# nanowii-i2c-mounting-board.net
KiCad netlist of a schematic drawn in EAGLE
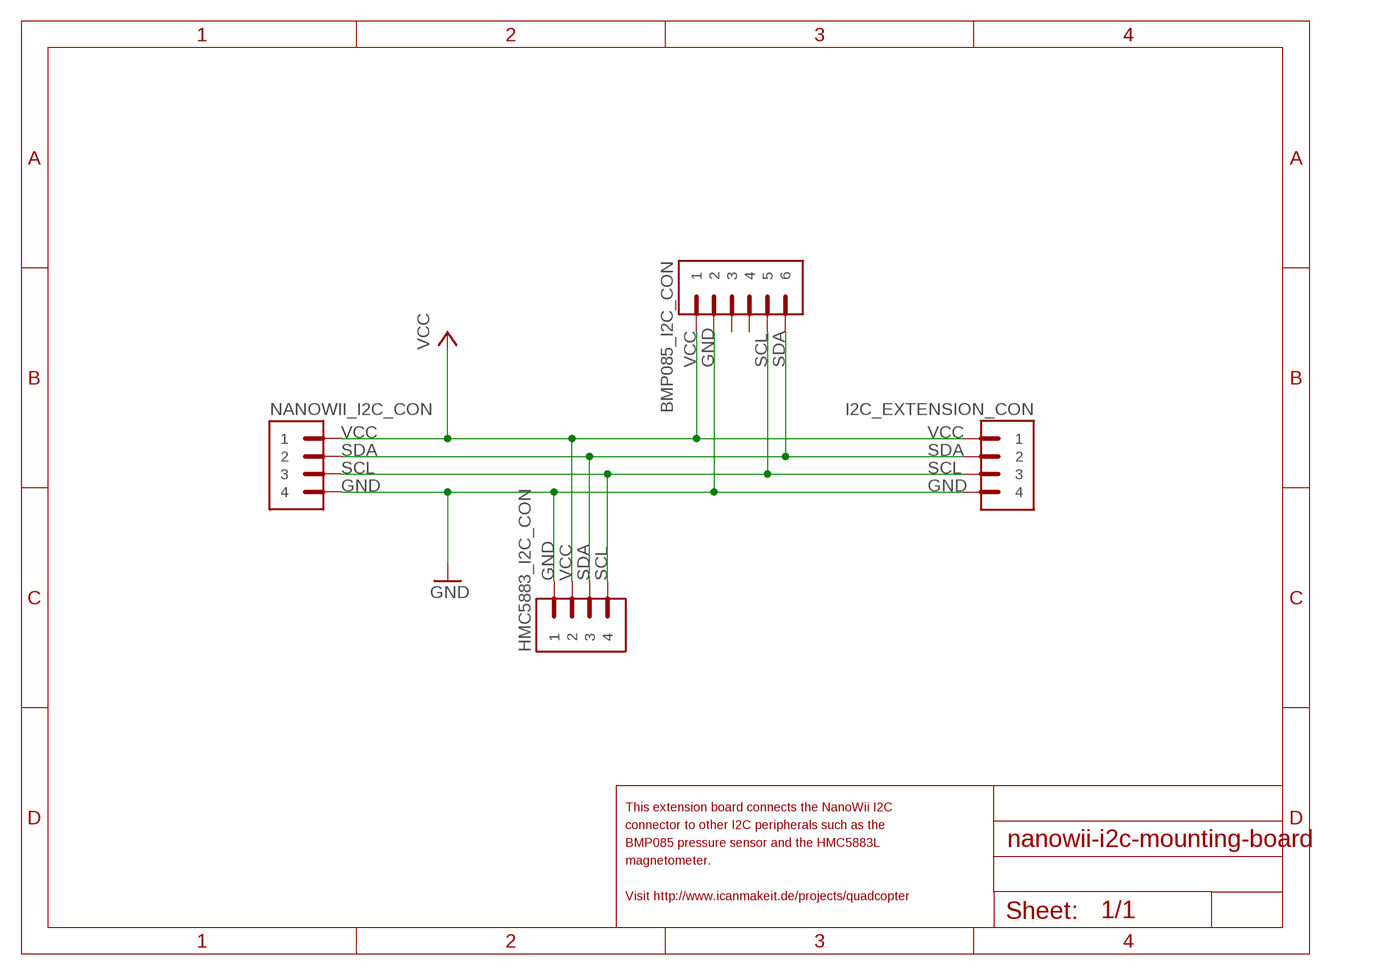
[diagram p0: schematic, sheet 1]

(export (version "E")
  (design (tool "Eeschema 10.0.6"))
  (components
    (comp (ref "BMP085_I2C_CON")
      (value "PIN_HEADER_6-WIDE")
      (footprint "eagle-import:BREAKAWAY_STRAIGHT_6_WIDE")
      (libsource (lib "eagle-import") (part "PIN_HEADER_6-WIDE"))
    )
    (comp (ref "HMC5883_I2C_CON")
      (value "PIN_HEADER_4-WIDE")
      (footprint "eagle-import:BREAKAWAY_STRAIGHT_4_WIDE")
      (libsource (lib "eagle-import") (part "PIN_HEADER_4-WIDE"))
    )
    (comp (ref "I2C_EXTENSION_CON")
      (value "PIN_HEADER_4-WIDE")
      (footprint "eagle-import:BREAKAWAY_STRAIGHT_4_WIDE")
      (libsource (lib "eagle-import") (part "PIN_HEADER_4-WIDE"))
    )
    (comp (ref "NANOWII_I2C_CON")
      (value "PIN_HEADER_4-WIDE")
      (footprint "eagle-import:BREAKAWAY_STRAIGHT_4_WIDE")
      (libsource (lib "eagle-import") (part "PIN_HEADER_4-WIDE"))
    )
  )
  (nets
    (net (code "1") (name "/SCL") (class "Default")
      (node (ref "BMP085_I2C_CON") (pin "5") (pinfunction "5_5") (pintype "passive"))
      (node (ref "HMC5883_I2C_CON") (pin "4") (pinfunction "4_4") (pintype "bidirectional"))
      (node (ref "I2C_EXTENSION_CON") (pin "3") (pinfunction "3_3") (pintype "bidirectional"))
      (node (ref "NANOWII_I2C_CON") (pin "3") (pinfunction "3_3") (pintype "bidirectional"))
    )
    (net (code "2") (name "/SDA") (class "Default")
      (node (ref "BMP085_I2C_CON") (pin "6") (pinfunction "6_6") (pintype "passive"))
      (node (ref "HMC5883_I2C_CON") (pin "3") (pinfunction "3_3") (pintype "bidirectional"))
      (node (ref "I2C_EXTENSION_CON") (pin "2") (pinfunction "2_2") (pintype "bidirectional"))
      (node (ref "NANOWII_I2C_CON") (pin "2") (pinfunction "2_2") (pintype "bidirectional"))
    )
    (net (code "3") (name "GND") (class "Default")
      (node (ref "BMP085_I2C_CON") (pin "2") (pinfunction "2_2") (pintype "passive"))
      (node (ref "HMC5883_I2C_CON") (pin "1") (pinfunction "1_1") (pintype "bidirectional"))
      (node (ref "I2C_EXTENSION_CON") (pin "4") (pinfunction "4_4") (pintype "bidirectional"))
      (node (ref "NANOWII_I2C_CON") (pin "4") (pinfunction "4_4") (pintype "bidirectional"))
    )
    (net (code "4") (name "VCC") (class "Default")
      (node (ref "BMP085_I2C_CON") (pin "1") (pinfunction "1_1") (pintype "passive"))
      (node (ref "HMC5883_I2C_CON") (pin "2") (pinfunction "2_2") (pintype "bidirectional"))
      (node (ref "I2C_EXTENSION_CON") (pin "1") (pinfunction "1_1") (pintype "bidirectional"))
      (node (ref "NANOWII_I2C_CON") (pin "1") (pinfunction "1_1") (pintype "bidirectional"))
    )
    (net (code "5") (name "unconnected-(BMP085_I2C_CON-Pad3)") (class "Default")
      (node (ref "BMP085_I2C_CON") (pin "3") (pinfunction "3_3") (pintype "passive"))
    )
    (net (code "6") (name "unconnected-(BMP085_I2C_CON-Pad4)") (class "Default")
      (node (ref "BMP085_I2C_CON") (pin "4") (pinfunction "4_4") (pintype "passive"))
    )
  )
)
